# Boost_Convertor_V1_Schematic.net
KiCad netlist of a schematic drawn in Altium Designer
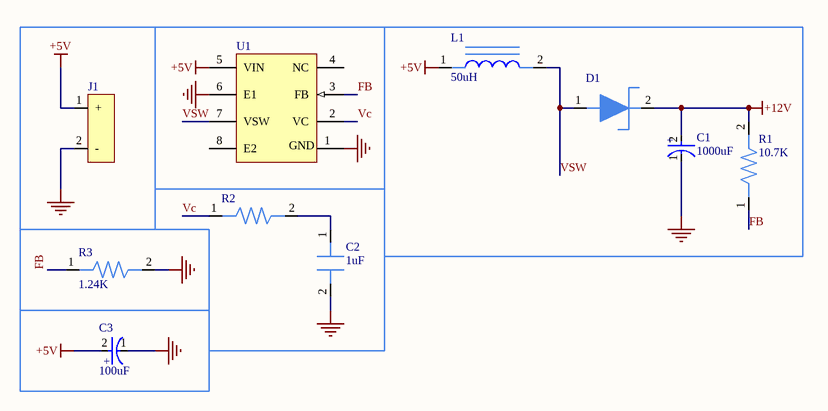
[diagram p0: Boost Convertor V1 Schematic.SchDoc]

(export (version "E")
  (design (tool "Eeschema 10.0.6"))
  (components
    (comp (ref "C1")
      (value "1000uF")
      (footprint "25PX1000MEFCT810X16")
      (fields
        (field (name "MANUFACTURER") "Rubycon")
        (field (name "MANUFACTURER PART NUMBER") "16ZLH1000MEFC10X16")
      )
      (libsource (lib "Boost") (part "16ZLH1000MEFC10X16"))
    )
    (comp (ref "C2")
      (value "1uF")
      (footprint "C1210C105K5RACTU")
      (description "Ceramic Capacitor 1uF")
      (fields
        (field (name "MANUFACTURER") "KEMET")
        (field (name "MANUFACTURER PART NUMBER") "ESL105M100AC3AA")
      )
      (libsource (lib "Boost") (part "CL10B105KA8NNNC"))
    )
    (comp (ref "C3")
      (value "100uF")
      (footprint "35ZLH100MEFC6.3X11")
      (description "CAP ALUM 100UF 20% 35V RADIAL")
      (fields (field (name "VOLTAGE") "35V") (field (name "TOLERANCE") "20%"))
      (libsource (lib "Boost") (part "a00bbbee19879c290e62620ae7e47b1"))
    )
    (comp (ref "D1")
      (value "BAT1000-7-F")
      (footprint "BAT1000-7-F")
      (description "Diode 40 V 1A Surface Mount SOT-23-3")
      (fields (field (name "MANUFACTURER") "Diodes"))
      (libsource (lib "Boost") (part "BAT1000-7-F"))
    )
    (comp (ref "J1") (value "0022013037") (libsource (lib "Boost") (part "Molex Connector")))
    (comp (ref "L1")
      (value "50uH")
      (footprint "CTX50-1-52-R")
      (description "General Purpose Inductor, 50uH, 1 Element, Iron-Core")
      (fields
        (field (name "MANUFACTURER") "Eaton Cooper")
        (field (name "MANUFACTURER PART NUMBER") "CTX50-1-52-R")
      )
      (libsource (lib "Boost") (part "CTX50-1-52-R"))
    )
    (comp (ref "R1")
      (value "10.7K")
      (footprint "RC0805FR-0710K7L")
      (description "Fixed Resistor, Metal Film, 0.25W, 10700ohm, 250V, 1% +/-Tol, -100,100ppm/Cel")
      (fields
        (field (name "MANUFACTURER") "Yageo")
        (field (name "MANUFACTURER PART NUMBER") "MFR-25FBF52-10K7")
      )
      (libsource (lib "Boost") (part "RC0805FR-0710K7L"))
    )
    (comp (ref "R2")
      (value "~")
      (footprint "RC0805FR-071KL")
      (description "Fixed Resistor, Carbon Film, 0.25W, 1000ohm, 350V, 5% +/-Tol, -400,0ppm/Cel, Through Hole Mount")
      (fields
        (field (name "MANUFACTURER") "Stackpole Electronics")
        (field (name "MANUFACTURER PART NUMBER") "CF14JT1K00")
      )
      (libsource (lib "Boost") (part "RC0805FR-071KL"))
    )
    (comp (ref "R3")
      (value "1.24K")
      (footprint "RC0805FR-071K24L")
      (description "Fixed Resistor, Metal Film, 0.25W, 1240ohm, 250V, 1% +/-Tol, -100,100ppm/Cel")
      (fields
        (field (name "MANUFACTURER") "Yageo")
        (field (name "MANUFACTURER PART NUMBER") "MFR-25FBF52-1K24")
      )
      (libsource (lib "Boost") (part "RC0805FR-071K24L"))
    )
    (comp (ref "U1")
      (value "LT1172CN8#PBF")
      (footprint "LT1172CN8#PBF-ND")
      (description "100 kHz, 1.25 A, High Efficiency Switching Regulator, 8-pin DIP (N8-8), 0 to 100 degC, Pb-Free")
      (fields (field (name "MANUFACTURER") "Linear Technology"))
      (libsource (lib "Boost") (part "LT-LT1172-X8-8"))
    )
  )
  (nets
    (net (code "1") (name "+5V") (class "Default")
      (node (ref "C3") (pin "2") (pinfunction "A_2") (pintype "passive"))
      (node (ref "J1") (pin "1") (pinfunction "+_1") (pintype "passive"))
      (node (ref "L1") (pin "1") (pinfunction "1_1") (pintype "passive"))
      (node (ref "U1") (pin "5") (pinfunction "VIN_5") (pintype "power_in"))
    )
    (net (code "2") (name "+12V") (class "Default")
      (node (ref "C1") (pin "2") (pinfunction "A_2") (pintype "passive"))
      (node (ref "D1") (pin "2") (pinfunction "2_2") (pintype "passive"))
      (node (ref "R1") (pin "2") (pinfunction "2_2") (pintype "passive"))
    )
    (net (code "3") (name "/FB") (class "Default")
      (node (ref "R1") (pin "1") (pinfunction "1_1") (pintype "passive"))
      (node (ref "R3") (pin "1") (pinfunction "1_1") (pintype "passive"))
      (node (ref "U1") (pin "3") (pinfunction "FB_3") (pintype "input"))
    )
    (net (code "4") (name "/VSW") (class "Default")
      (node (ref "D1") (pin "1") (pinfunction "1_1") (pintype "passive"))
      (node (ref "L1") (pin "2") (pinfunction "2_2") (pintype "passive"))
      (node (ref "U1") (pin "7") (pinfunction "VSW_7") (pintype "power_in"))
    )
    (net (code "5") (name "/Vc") (class "Default")
      (node (ref "R2") (pin "1") (pinfunction "1_1") (pintype "passive"))
      (node (ref "U1") (pin "2") (pinfunction "VC_2") (pintype "passive"))
    )
    (net (code "6") (name "GND") (class "Default")
      (node (ref "C1") (pin "1") (pinfunction "C_1") (pintype "passive"))
      (node (ref "C2") (pin "2") (pinfunction "2_2") (pintype "passive"))
      (node (ref "C3") (pin "1") (pinfunction "C_1") (pintype "passive"))
      (node (ref "J1") (pin "2") (pinfunction "-_2") (pintype "passive"))
      (node (ref "R3") (pin "2") (pinfunction "2_2") (pintype "passive"))
      (node (ref "U1") (pin "6") (pinfunction "E1_6") (pintype "passive"))
    )
    (net (code "7") (name "Net-(C2-Pad1)") (class "Default")
      (node (ref "C2") (pin "1") (pinfunction "1_1") (pintype "passive"))
      (node (ref "R2") (pin "2") (pinfunction "2_2") (pintype "passive"))
    )
    (net (code "8") (name "unconnected-(U1-E2-Pad8)") (class "Default")
      (node (ref "U1") (pin "8") (pinfunction "E2_8") (pintype "passive"))
    )
    (net (code "9") (name "unconnected-(U1-GND-Pad1)") (class "Default")
      (node (ref "U1") (pin "1") (pinfunction "GND_1") (pintype "power_in"))
    )
    (net (code "10") (name "unconnected-(U1-NC-Pad4)") (class "Default")
      (node (ref "U1") (pin "4") (pinfunction "NC_4") (pintype "passive"))
    )
  )
)
